# Bidirect_convertor.net
KiCad netlist of a schematic drawn in Altium Designer
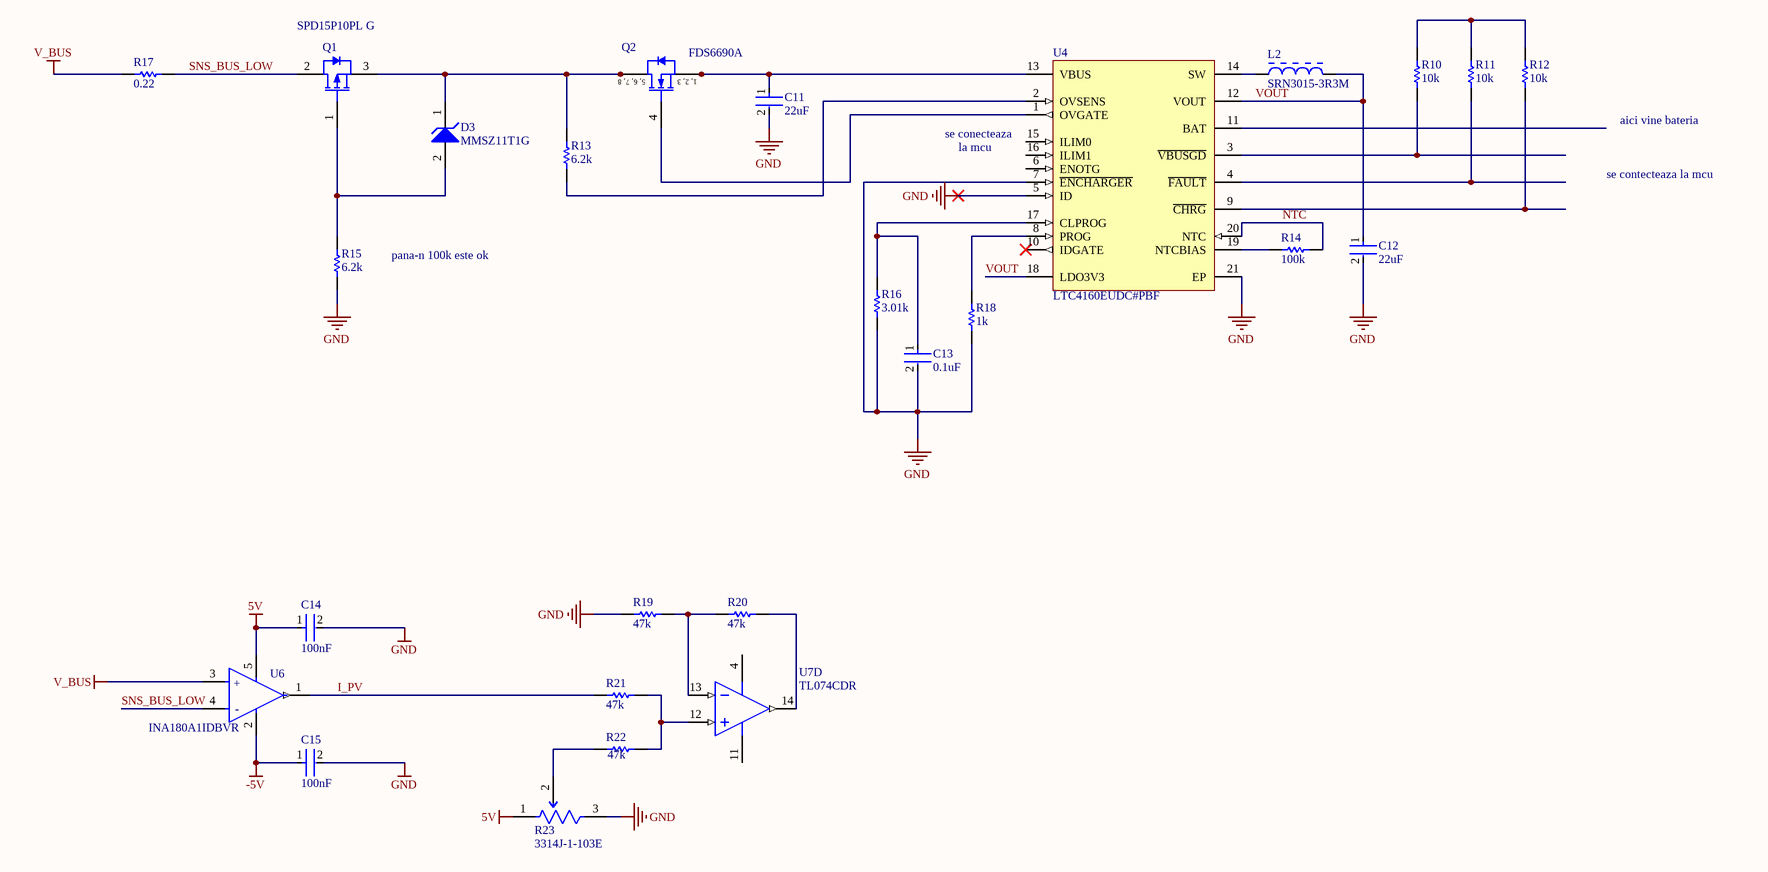
[diagram p0: Bidirect_convertor.SchDoc]

(export (version "E")
  (design (tool "Eeschema 10.0.6"))
  (components
    (comp (ref "C11")
      (value "22uF")
      (footprint "FP-C2012-125-0_2-IPC_C")
      (description "Multilayer Ceramic Capacitors 22μF ±10% 16V X5R SMD 0805")
      (fields (field (name "TOLERANCE") "10%") (field (name "VOLTAGE") "16V"))
      (libsource (lib "Altium Content Vault") (part "b4654b650e69147ec39a6b967a45e02"))
    )
    (comp (ref "C12")
      (value "22uF")
      (footprint "FP-C2012-125-0_2-IPC_C")
      (description "Multilayer Ceramic Capacitors 22μF ±10% 16V X5R SMD 0805")
      (fields (field (name "TOLERANCE") "10%") (field (name "VOLTAGE") "16V"))
      (libsource (lib "Altium Content Vault") (part "b4654b650e69147ec39a6b967a45e02"))
    )
    (comp (ref "C13")
      (value "0.1uF")
      (footprint "FP-GRM155-0_05-MFG")
      (description "CAP CER 0.1UF 16V X7R 0402")
      (fields (field (name "TOLERANCE") "5%") (field (name "VOLTAGE") "16V"))
      (libsource (lib "Altium Content Vault") (part "02cd4be3c70576c341d710602a673aa"))
    )
    (comp (ref "C14")
      (value "100nF")
      (footprint "FP-CGA3E-0_3-0_1-IPC_A")
      (description "Cap Ceramic 100nF 50V X7R 10% Pad SMD 0603 +125°C Automotive T/R")
      (fields (field (name "TOLERANCE") "10%") (field (name "VOLTAGE") "50V"))
      (libsource (lib "Altium Content Vault") (part "b4654b650e69147ec39a6b967a45e02"))
    )
    (comp (ref "C15")
      (value "100nF")
      (footprint "FP-CGA3E-0_3-0_1-IPC_A")
      (description "Cap Ceramic 100nF 50V X7R 10% Pad SMD 0603 +125°C Automotive T/R")
      (fields (field (name "TOLERANCE") "10%") (field (name "VOLTAGE") "50V"))
      (libsource (lib "Altium Content Vault") (part "b4654b650e69147ec39a6b967a45e02"))
    )
    (comp (ref "D3")
      (value "MMSZ11T1G")
      (footprint "ONSC-SOD-123-2-425-04_V")
      (description "Zener Voltage Regulator, 500 mW, 2-Pin SOD-123, Pb-Free, Tape and Reel")
      (fields (field (name "MANUFACTURER") "On Semiconductor"))
      (libsource (lib "Altium Content Vault") (part "ONSC-K1A2-2"))
    )
    (comp (ref "L2")
      (value "SRN3015-3R3M")
      (footprint "BOUR-SRN3015-2_V")
      (fields (field (name "MANUFACTURER") "Bourns"))
      (libsource (lib "Altium Content Vault") (part "BOUR-IND-2A"))
    )
    (comp (ref "Q1")
      (value "SPD15P10PL G")
      (footprint "INF-PG-TO252-3-1_N")
      (fields (field (name "MANUFACTURER") "Infineon"))
      (libsource (lib "Altium Content Vault") (part "INF-PEMOS-GDS-3"))
    )
    (comp (ref "Q2")
      (value "FDS6690A")
      (footprint "FAIR-SOIC-8_V")
      (fields (field (name "MANUFACTURER") "Fairchild Semiconductor"))
      (libsource (lib "Altium Content Vault") (part "NEMOS-SSSGDDDD-8"))
    )
    (comp (ref "R10")
      (value "10k")
      (footprint "RESC1609X55X30LL15T15")
      (description "Chip Resistor, 10 KOhm, +/- 1%, 0.1 W, -55 to 155 degC, 0603 (1608 Metric), RoHS, Tape and Reel")
      (fields (field (name "TOLERANCE") "1%") (field (name "MANUFACTURER") "Panasonic"))
      (libsource (lib "Altium Content Vault") (part "RES-2"))
    )
    (comp (ref "R11")
      (value "10k")
      (footprint "RESC1609X55X30LL15T15")
      (description "Chip Resistor, 10 KOhm, +/- 1%, 0.1 W, -55 to 155 degC, 0603 (1608 Metric), RoHS, Tape and Reel")
      (fields (field (name "TOLERANCE") "1%") (field (name "MANUFACTURER") "Panasonic"))
      (libsource (lib "Altium Content Vault") (part "RES-2"))
    )
    (comp (ref "R12")
      (value "10k")
      (footprint "RESC1609X55X30LL15T15")
      (description "Chip Resistor, 10 KOhm, +/- 1%, 0.1 W, -55 to 155 degC, 0603 (1608 Metric), RoHS, Tape and Reel")
      (fields (field (name "TOLERANCE") "1%") (field (name "MANUFACTURER") "Panasonic"))
      (libsource (lib "Altium Content Vault") (part "RES-2"))
    )
    (comp (ref "R13")
      (value "6.2k")
      (footprint "RESC1609X50X30ML10T20")
      (fields (field (name "PART NUMBER") "CRCW06036K20FKEA") (field (name "MANUFACTURER") "Vishay Dale"))
      (libsource (lib "Altium Content Vault") (part "RES"))
    )
    (comp (ref "R14")
      (value "100k")
      (footprint "RESC1608X55X30ML15T15")
      (fields (field (name "PART NUMBER") "ERJ-3EKF1003V") (field (name "MANUFACTURER") "Panasonic"))
      (libsource (lib "Altium Content Vault") (part "RES"))
    )
    (comp (ref "R15")
      (value "6.2k")
      (footprint "RESC1609X50X30ML10T20")
      (fields (field (name "PART NUMBER") "CRCW06036K20FKEA") (field (name "MANUFACTURER") "Vishay Dale"))
      (libsource (lib "Altium Content Vault") (part "RES"))
    )
    (comp (ref "R16")
      (value "3.01k")
      (footprint "RESC1608X55X30LL15T15")
      (fields (field (name "PART NUMBER") "ERJ-3EKF3011V") (field (name "MANUFACTURER") "Panasonic"))
      (libsource (lib "Altium Content Vault") (part "RES"))
    )
    (comp (ref "R17")
      (value "0.22")
      (footprint "RESC2013X70X40NL20T20")
      (fields (field (name "MANUFACTURER") "Panasonic") (field (name "PART NUMBER") "ERJ6RQFR22V"))
      (libsource (lib "Altium Content Vault") (part "RES"))
    )
    (comp (ref "R18")
      (value "1k")
      (footprint "RESC1608X55X30LL15T15")
      (fields (field (name "PART NUMBER") "ERJ-3EKF1001V") (field (name "MANUFACTURER") "Panasonic"))
      (libsource (lib "Altium Content Vault") (part "RES"))
    )
    (comp (ref "R19")
      (value "47k")
      (footprint "RESC1608X55X30NL15T15")
      (description "Chip Resistor, 47 KOhm, +/- 1%, 0.1 W, -55 to 155 degC, 0603 (1608 Metric), RoHS, Tape and Reel")
      (libsource (lib "Altium Content Vault") (part "RES-2"))
    )
    (comp (ref "R20")
      (value "47k")
      (footprint "RESC1608X55X30NL15T15")
      (description "Chip Resistor, 47 KOhm, +/- 1%, 0.1 W, -55 to 155 degC, 0603 (1608 Metric), RoHS, Tape and Reel")
      (libsource (lib "Altium Content Vault") (part "RES-2"))
    )
    (comp (ref "R21")
      (value "47k")
      (footprint "RESC1608X55X30NL15T15")
      (description "Chip Resistor, 47 KOhm, +/- 1%, 0.1 W, -55 to 155 degC, 0603 (1608 Metric), RoHS, Tape and Reel")
      (libsource (lib "Altium Content Vault") (part "RES-2"))
    )
    (comp (ref "R22")
      (value "47k")
      (footprint "RESC1608X55X30NL15T15")
      (description "Chip Resistor, 47 KOhm, +/- 1%, 0.1 W, -55 to 155 degC, 0603 (1608 Metric), RoHS, Tape and Reel")
      (libsource (lib "Altium Content Vault") (part "RES-2"))
    )
    (comp (ref "R23")
      (value "3314J-1-103E")
      (footprint "FP-3314J-1-MFG")
      (description "TRIMMER 10K OHM 0.25W J LEAD TOP")
      (libsource (lib "Altium Content Vault") (part "13357d81287629c2fd191d242cfa50c"))
    )
    (comp (ref "U4")
      (value "LTC4160EUDC#PBF")
      (footprint "LT-UDC-20_N")
      (fields (field (name "MANUFACTURER") "Linear Technology"))
      (libsource (lib "Altium Content Vault") (part "LT-LTC4160-UDC-20"))
    )
    (comp (ref "U6")
      (value "INA180A1IDBVR")
      (footprint "FP-DBV0005A-IPC_A")
      (description "IC CURR SENSE 1 CIRCUIT SOT23-5")
      (libsource (lib "Altium Content Vault") (part "0a55cf1a948ad01a3239aec1b7efad0"))
    )
    (comp (ref "U7")
      (value "TL074CDR")
      (footprint "D0014A_N")
      (fields (field (name "MANUFACTURER") "Texas Instruments"))
      (libsource (lib "Altium Content Vault") (part "TI-TLXX4X_MC3403-X14"))
    )
  )
  (nets
    (net (code "1") (name "-5V") (class "Default")
      (node (ref "C15") (pin "1") (pinfunction "1_1") (pintype "passive"))
      (node (ref "U6") (pin "2") (pinfunction "GND_2") (pintype "power_in"))
    )
    (net (code "2") (name "/I_PV") (class "Default")
      (node (ref "R21") (pin "2") (pinfunction "2_2") (pintype "passive"))
      (node (ref "U6") (pin "1") (pinfunction "OUT_1") (pintype "output"))
    )
    (net (code "3") (name "/NTC") (class "Default")
      (node (ref "R14") (pin "2") (pinfunction "2_2") (pintype "passive"))
      (node (ref "U4") (pin "20") (pinfunction "NTC_20") (pintype "input"))
    )
    (net (code "4") (name "/SNS_BUS_LOW") (class "Default")
      (node (ref "Q1") (pin "2") (pinfunction "DRAIN_2") (pintype "passive"))
      (node (ref "R17") (pin "2") (pinfunction "2_2") (pintype "passive"))
      (node (ref "U6") (pin "4") (pinfunction "IN-_4") (pintype "tri_state"))
    )
    (net (code "5") (name "/VOUT") (class "Default")
      (node (ref "C12") (pin "1") (pinfunction "1_1") (pintype "passive"))
      (node (ref "L2") (pin "2") (pinfunction "2_2") (pintype "passive"))
      (node (ref "U4") (pin "12") (pinfunction "VOUT_12") (pintype "power_in"))
      (node (ref "U4") (pin "18") (pinfunction "LDO3V3_18") (pintype "power_in"))
    )
    (net (code "6") (name "5V") (class "Default")
      (node (ref "C14") (pin "1") (pinfunction "1_1") (pintype "passive"))
      (node (ref "R23") (pin "1") (pinfunction "CCW_1") (pintype "passive"))
      (node (ref "U6") (pin "5") (pinfunction "VS_5") (pintype "power_in"))
    )
    (net (code "7") (name "GND") (class "Default")
      (node (ref "C11") (pin "2") (pinfunction "2_2") (pintype "passive"))
      (node (ref "C12") (pin "2") (pinfunction "2_2") (pintype "passive"))
      (node (ref "C13") (pin "2") (pinfunction "2_2") (pintype "passive"))
      (node (ref "C14") (pin "2") (pinfunction "2_2") (pintype "passive"))
      (node (ref "C15") (pin "2") (pinfunction "2_2") (pintype "passive"))
      (node (ref "R15") (pin "1") (pinfunction "1_1") (pintype "passive"))
      (node (ref "R16") (pin "1") (pinfunction "1_1") (pintype "passive"))
      (node (ref "R18") (pin "1") (pinfunction "1_1") (pintype "passive"))
      (node (ref "R19") (pin "2") (pinfunction "2_2") (pintype "passive"))
      (node (ref "R23") (pin "3") (pinfunction "CW_3") (pintype "passive"))
      (node (ref "U4") (pin "21") (pinfunction "EP_21") (pintype "power_in"))
      (node (ref "U4") (pin "5") (pinfunction "ID_5") (pintype "input"))
      (node (ref "U4") (pin "7") (pinfunction "~{ENCHARGER}_7") (pintype "input"))
    )
    (net (code "8") (name "Net-(D3-A)") (class "Default")
      (node (ref "D3") (pin "2") (pinfunction "A_2") (pintype "passive"))
      (node (ref "Q1") (pin "1") (pinfunction "GATE_1") (pintype "passive"))
      (node (ref "R15") (pin "2") (pinfunction "2_2") (pintype "passive"))
    )
    (net (code "9") (name "Net-(D3-K)") (class "Default")
      (node (ref "D3") (pin "1") (pinfunction "K_1") (pintype "passive"))
      (node (ref "Q1") (pin "3") (pinfunction "SOURCE_3") (pintype "passive"))
      (node (ref "Q2") (pin "5") (pinfunction "D_5") (pintype "passive"))
      (node (ref "Q2") (pin "6") (pinfunction "D_6") (pintype "passive"))
      (node (ref "Q2") (pin "7") (pinfunction "D_7") (pintype "passive"))
      (node (ref "Q2") (pin "8") (pinfunction "D_8") (pintype "passive"))
      (node (ref "R13") (pin "2") (pinfunction "2_2") (pintype "passive"))
    )
    (net (code "10") (name "Net-(Q2-G)") (class "Default")
      (node (ref "Q2") (pin "4") (pinfunction "G_4") (pintype "passive"))
      (node (ref "U4") (pin "1") (pinfunction "OVGATE_1") (pintype "output"))
    )
    (net (code "11") (name "Net-(R10-Pad2)") (class "Default")
      (node (ref "R10") (pin "2") (pinfunction "2_2") (pintype "passive"))
      (node (ref "R11") (pin "2") (pinfunction "2_2") (pintype "passive"))
      (node (ref "R12") (pin "2") (pinfunction "2_2") (pintype "passive"))
    )
    (net (code "12") (name "Net-(R23-WIPER)") (class "Default")
      (node (ref "R22") (pin "2") (pinfunction "2_2") (pintype "passive"))
      (node (ref "R23") (pin "2") (pinfunction "WIPER_2") (pintype "passive"))
    )
    (net (code "13") (name "Net-(U4-CLPROG)") (class "Default")
      (node (ref "C13") (pin "1") (pinfunction "1_1") (pintype "passive"))
      (node (ref "R16") (pin "2") (pinfunction "2_2") (pintype "passive"))
      (node (ref "U4") (pin "17") (pinfunction "CLPROG_17") (pintype "input"))
    )
    (net (code "14") (name "Net-(U4-NTCBIAS)") (class "Default")
      (node (ref "R14") (pin "1") (pinfunction "1_1") (pintype "passive"))
      (node (ref "U4") (pin "19") (pinfunction "NTCBIAS_19") (pintype "passive"))
    )
    (net (code "15") (name "Net-(U4-OVSENS)") (class "Default")
      (node (ref "R13") (pin "1") (pinfunction "1_1") (pintype "passive"))
      (node (ref "U4") (pin "2") (pinfunction "OVSENS_2") (pintype "input"))
    )
    (net (code "16") (name "Net-(U4-PROG)") (class "Default")
      (node (ref "R18") (pin "2") (pinfunction "2_2") (pintype "passive"))
      (node (ref "U4") (pin "8") (pinfunction "PROG_8") (pintype "input"))
    )
    (net (code "17") (name "Net-(U4-SW)") (class "Default")
      (node (ref "L2") (pin "1") (pinfunction "1_1") (pintype "passive"))
      (node (ref "U4") (pin "14") (pinfunction "SW_14") (pintype "power_in"))
    )
    (net (code "18") (name "Net-(U4-VBUS)") (class "Default")
      (node (ref "C11") (pin "1") (pinfunction "1_1") (pintype "passive"))
      (node (ref "Q2") (pin "1") (pinfunction "S_1") (pintype "passive"))
      (node (ref "Q2") (pin "2") (pinfunction "S_2") (pintype "passive"))
      (node (ref "Q2") (pin "3") (pinfunction "S_3") (pintype "passive"))
      (node (ref "U4") (pin "13") (pinfunction "VBUS_13") (pintype "power_in"))
    )
    (net (code "19") (name "Net-(U4-~{CHRG})") (class "Default")
      (node (ref "R12") (pin "1") (pinfunction "1_1") (pintype "passive"))
      (node (ref "U4") (pin "9") (pinfunction "~{CHRG}_9") (pintype "open_collector"))
    )
    (net (code "20") (name "Net-(U4-~{FAULT})") (class "Default")
      (node (ref "R11") (pin "1") (pinfunction "1_1") (pintype "passive"))
      (node (ref "U4") (pin "4") (pinfunction "~{FAULT}_4") (pintype "open_collector"))
    )
    (net (code "21") (name "Net-(U4-~{VBUSGD})") (class "Default")
      (node (ref "R10") (pin "1") (pinfunction "1_1") (pintype "passive"))
      (node (ref "U4") (pin "3") (pinfunction "~{VBUSGD}_3") (pintype "open_collector"))
    )
    (net (code "22") (name "Net-(U7D-IN4+)") (class "Default")
      (node (ref "R21") (pin "1") (pinfunction "1_1") (pintype "passive"))
      (node (ref "R22") (pin "1") (pinfunction "1_1") (pintype "passive"))
      (node (ref "U7") (pin "12") (pinfunction "IN4+_12") (pintype "input"))
    )
    (net (code "23") (name "Net-(U7D-IN4-)") (class "Default")
      (node (ref "R19") (pin "1") (pinfunction "1_1") (pintype "passive"))
      (node (ref "R20") (pin "2") (pinfunction "2_2") (pintype "passive"))
      (node (ref "U7") (pin "13") (pinfunction "IN4-_13") (pintype "input"))
    )
    (net (code "24") (name "Net-(U7D-OUT4)") (class "Default")
      (node (ref "R20") (pin "1") (pinfunction "1_1") (pintype "passive"))
      (node (ref "U7") (pin "14") (pinfunction "OUT4_14") (pintype "output"))
    )
    (net (code "25") (name "V_BUS") (class "Default")
      (node (ref "R17") (pin "1") (pinfunction "1_1") (pintype "passive"))
      (node (ref "U6") (pin "3") (pinfunction "IN+_3") (pintype "tri_state"))
    )
    (net (code "26") (name "unconnected-(U4-BAT-Pad11)") (class "Default")
      (node (ref "U4") (pin "11") (pinfunction "BAT_11") (pintype "power_in"))
    )
    (net (code "27") (name "unconnected-(U4-ENOTG-Pad6)") (class "Default")
      (node (ref "U4") (pin "6") (pinfunction "ENOTG_6") (pintype "input"))
    )
    (net (code "28") (name "unconnected-(U4-IDGATE-Pad10)") (class "Default")
      (node (ref "U4") (pin "10") (pinfunction "IDGATE_10") (pintype "output+no_connect"))
    )
    (net (code "29") (name "unconnected-(U4-ILIM0-Pad15)") (class "Default")
      (node (ref "U4") (pin "15") (pinfunction "ILIM0_15") (pintype "input"))
    )
    (net (code "30") (name "unconnected-(U4-ILIM1-Pad16)") (class "Default")
      (node (ref "U4") (pin "16") (pinfunction "ILIM1_16") (pintype "input"))
    )
    (net (code "31") (name "unconnected-(U7D-VCC+-Pad4)") (class "Default")
      (node (ref "U7") (pin "4") (pinfunction "VCC+_4") (pintype "power_in"))
    )
    (net (code "32") (name "unconnected-(U7D-VCC--Pad11)") (class "Default")
      (node (ref "U7") (pin "11") (pinfunction "VCC-_11") (pintype "power_in"))
    )
  )
)
